# transducerVIS.net
KiCad netlist of a schematic drawn in EAGLE
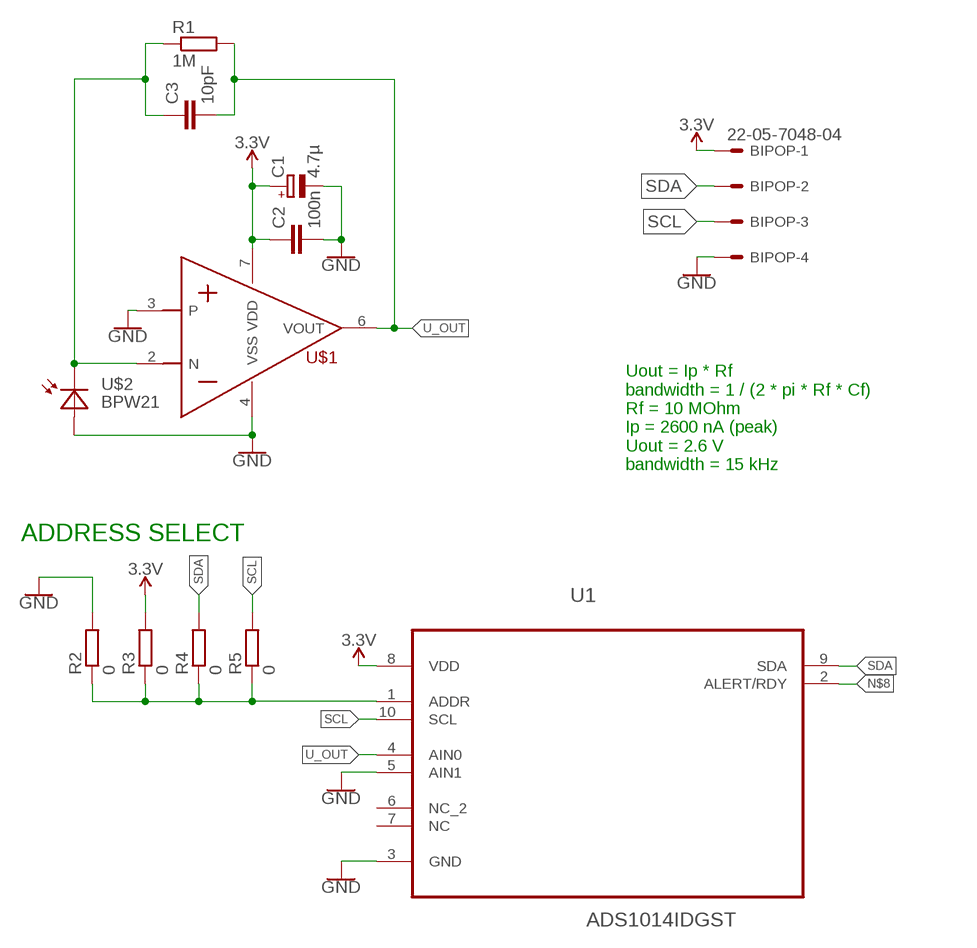
[diagram p0: schematic, sheet 1]

(export (version "E")
  (design (tool "Eeschema 10.0.6"))
  (components
    (comp (ref "BIPOP")
      (value "22-05-7048-04")
      (footprint "eagle-import:7395-04")
      (libsource (lib "eagle-import") (part "22-?-0405-7048"))
    )
    (comp (ref "C1")
      (value "4.7µ")
      (footprint "eagle-import:A_3216-18R")
      (libsource (lib "eagle-import") (part "CPOL-EUA/3216-18R"))
    )
    (comp (ref "C2")
      (value "100n")
      (footprint "eagle-import:C0805")
      (libsource (lib "eagle-import") (part "resistor_348_C-EUC0805"))
    )
    (comp (ref "C3")
      (value "10pF")
      (footprint "eagle-import:C0603")
      (libsource (lib "eagle-import") (part "C-EUC0603"))
    )
    (comp (ref "R1")
      (value "1M")
      (footprint "eagle-import:R0805")
      (libsource (lib "eagle-import") (part "R-EU_R0805"))
    )
    (comp (ref "R2")
      (value "0")
      (footprint "eagle-import:R0805")
      (libsource (lib "eagle-import") (part "R-EU_R0805"))
    )
    (comp (ref "R3")
      (value "0")
      (footprint "eagle-import:R0805")
      (libsource (lib "eagle-import") (part "R-EU_R0805"))
    )
    (comp (ref "R4")
      (value "0")
      (footprint "eagle-import:R0805")
      (libsource (lib "eagle-import") (part "R-EU_R0805"))
    )
    (comp (ref "R5")
      (value "0")
      (footprint "eagle-import:R0805")
      (libsource (lib "eagle-import") (part "R-EU_R0805"))
    )
    (comp (ref "U$1")
      (value "LMC6001")
      (footprint "eagle-import:DIL08")
      (libsource (lib "eagle-import") (part "LMC6001"))
    )
    (comp (ref "U$2")
      (value "BPW21")
      (footprint "eagle-import:TO52")
      (libsource (lib "eagle-import") (part "BPW21"))
    )
    (comp (ref "U1")
      (value "ADS1014IDGST")
      (footprint "eagle-import:SOP50P490X110-10N")
      (libsource (lib "eagle-import") (part "ADS1014IDGST"))
    )
  )
  (nets
    (net (code "1") (name "3.3V") (class "Default")
      (node (ref "BIPOP") (pin "1") (pinfunction "S_1") (pintype "passive"))
      (node (ref "C1") (pin "+") (pinfunction "+_+") (pintype "passive"))
      (node (ref "C2") (pin "1") (pinfunction "1_1") (pintype "passive"))
      (node (ref "R3") (pin "2") (pinfunction "2_2") (pintype "passive"))
      (node (ref "U$1") (pin "7") (pinfunction "VDD_7") (pintype "power_in"))
      (node (ref "U1") (pin "8") (pinfunction "VDD_8") (pintype "power_in"))
    )
    (net (code "2") (name "GND") (class "Default")
      (node (ref "BIPOP") (pin "4") (pinfunction "S_4") (pintype "passive"))
      (node (ref "C1") (pin "-") (pinfunction "-_-") (pintype "passive"))
      (node (ref "C2") (pin "2") (pinfunction "2_2") (pintype "passive"))
      (node (ref "R2") (pin "2") (pinfunction "2_2") (pintype "passive"))
      (node (ref "U$1") (pin "3") (pinfunction "P_3") (pintype "bidirectional"))
      (node (ref "U$1") (pin "4") (pinfunction "VSS_4") (pintype "power_in"))
      (node (ref "U$2") (pin "1") (pinfunction "A_1") (pintype "passive"))
      (node (ref "U1") (pin "3") (pinfunction "GND_3") (pintype "passive"))
      (node (ref "U1") (pin "5") (pinfunction "AIN1_5") (pintype "input"))
    )
    (net (code "3") (name "N$8") (class "Default")
      (node (ref "U1") (pin "2") (pinfunction "ALERT/RDY_2") (pintype "output"))
    )
    (net (code "4") (name "Net-(U$1-N)") (class "Default")
      (node (ref "C3") (pin "1") (pinfunction "1_1") (pintype "passive"))
      (node (ref "R1") (pin "1") (pinfunction "1_1") (pintype "passive"))
      (node (ref "U$1") (pin "2") (pinfunction "N_2") (pintype "bidirectional"))
      (node (ref "U$2") (pin "2") (pinfunction "C_2") (pintype "passive"))
    )
    (net (code "5") (name "Net-(U1-ADDR)") (class "Default")
      (node (ref "R2") (pin "1") (pinfunction "1_1") (pintype "passive"))
      (node (ref "R3") (pin "1") (pinfunction "1_1") (pintype "passive"))
      (node (ref "R4") (pin "1") (pinfunction "1_1") (pintype "passive"))
      (node (ref "R5") (pin "1") (pinfunction "1_1") (pintype "passive"))
      (node (ref "U1") (pin "1") (pinfunction "ADDR_1") (pintype "input"))
    )
    (net (code "6") (name "SCL") (class "Default")
      (node (ref "BIPOP") (pin "3") (pinfunction "S_3") (pintype "passive"))
      (node (ref "R5") (pin "2") (pinfunction "2_2") (pintype "passive"))
      (node (ref "U1") (pin "10") (pinfunction "SCL_10") (pintype "input"))
    )
    (net (code "7") (name "SDA") (class "Default")
      (node (ref "BIPOP") (pin "2") (pinfunction "S_2") (pintype "passive"))
      (node (ref "R4") (pin "2") (pinfunction "2_2") (pintype "passive"))
      (node (ref "U1") (pin "9") (pinfunction "SDA_9") (pintype "bidirectional"))
    )
    (net (code "8") (name "U_OUT") (class "Default")
      (node (ref "C3") (pin "2") (pinfunction "2_2") (pintype "passive"))
      (node (ref "R1") (pin "2") (pinfunction "2_2") (pintype "passive"))
      (node (ref "U$1") (pin "6") (pinfunction "VOUT_6") (pintype "bidirectional"))
      (node (ref "U1") (pin "4") (pinfunction "AIN0_4") (pintype "input"))
    )
    (net (code "9") (name "unconnected-(U1-NC-Pad7)") (class "Default")
      (node (ref "U1") (pin "7") (pinfunction "NC_7") (pintype "no_connect"))
    )
    (net (code "10") (name "unconnected-(U1-NC_2-Pad6)") (class "Default")
      (node (ref "U1") (pin "6") (pinfunction "NC_2_6") (pintype "no_connect"))
    )
  )
)
